# trabalho.net
KiCad netlist of a schematic drawn in EAGLE
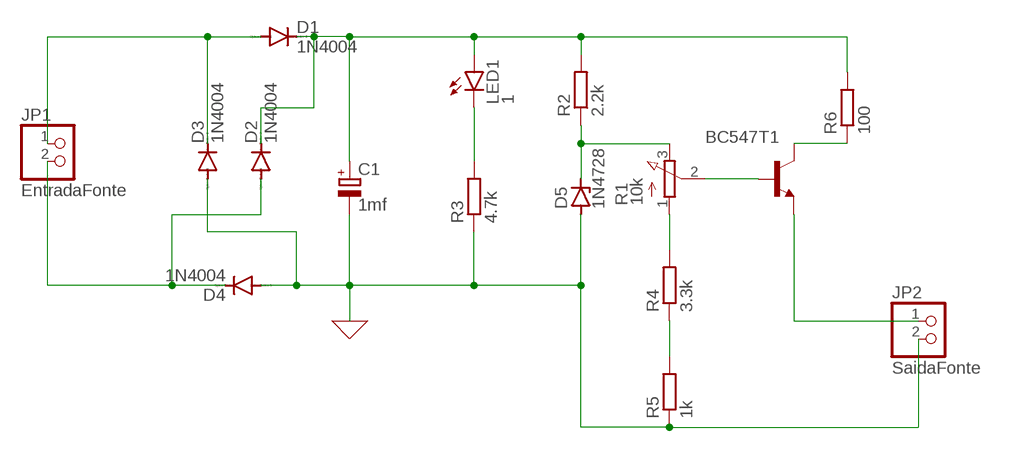
[diagram p0: schematic, sheet 1]

(export (version "E")
  (design (tool "Eeschema 10.0.6"))
  (components
    (comp (ref "C1")
      (value "1mf")
      (footprint "eagle-import:E5-10,5")
      (libsource (lib "eagle-import") (part "CPOL-EUE5-10.5"))
    )
    (comp (ref "D1")
      (value "1N4004")
      (footprint "eagle-import:DO41-10")
      (libsource (lib "eagle-import") (part "1N4004"))
    )
    (comp (ref "D2")
      (value "1N4004")
      (footprint "eagle-import:DO41-10")
      (libsource (lib "eagle-import") (part "1N4004"))
    )
    (comp (ref "D3")
      (value "1N4004")
      (footprint "eagle-import:DO41-10")
      (libsource (lib "eagle-import") (part "1N4004"))
    )
    (comp (ref "D4")
      (value "1N4004")
      (footprint "eagle-import:DO41-10")
      (libsource (lib "eagle-import") (part "1N4004"))
    )
    (comp (ref "D5")
      (value "1N4728")
      (footprint "eagle-import:DO41Z10")
      (libsource (lib "eagle-import") (part "1N4728"))
    )
    (comp (ref "JP1")
      (value "EntradaFonte")
      (footprint "eagle-import:1X02")
      (libsource (lib "eagle-import") (part "PINHD-1X2"))
    )
    (comp (ref "JP2")
      (value "SaidaFonte")
      (footprint "eagle-import:1X02")
      (libsource (lib "eagle-import") (part "PINHD-1X2"))
    )
    (comp (ref "LED1")
      (value "1")
      (footprint "eagle-import:LED5MM")
      (libsource (lib "eagle-import") (part "LED5MM"))
    )
    (comp (ref "R1")
      (value "10k")
      (footprint "eagle-import:3RP_1610N")
      (libsource (lib "eagle-import") (part "3RP/1610N"))
    )
    (comp (ref "R2")
      (value "2.2k")
      (footprint "eagle-import:0207_10")
      (libsource (lib "eagle-import") (part "R-EU_0207/10"))
    )
    (comp (ref "R3")
      (value "4.7k")
      (footprint "eagle-import:0207_10")
      (libsource (lib "eagle-import") (part "R-EU_0207/10"))
    )
    (comp (ref "R4")
      (value "3.3k")
      (footprint "eagle-import:0207_10")
      (libsource (lib "eagle-import") (part "R-EU_0207/10"))
    )
    (comp (ref "R5")
      (value "1k")
      (footprint "eagle-import:0207_10")
      (libsource (lib "eagle-import") (part "R-EU_0207/10"))
    )
    (comp (ref "R6")
      (value "100")
      (footprint "eagle-import:0207_10")
      (libsource (lib "eagle-import") (part "R-EU_0207/10"))
    )
    (comp (ref "T1")
      (value "BC547")
      (footprint "eagle-import:TO92")
      (libsource (lib "eagle-import") (part "BC547"))
    )
  )
  (nets
    (net (code "1") (name "GND") (class "Default")
      (node (ref "C1") (pin "-") (pinfunction "-_-") (pintype "passive"))
      (node (ref "D3") (pin "A") (pinfunction "A_A") (pintype "passive"))
      (node (ref "D4") (pin "A") (pinfunction "A_A") (pintype "passive"))
      (node (ref "D5") (pin "A") (pinfunction "A_A") (pintype "passive"))
      (node (ref "JP2") (pin "2") (pinfunction "2_2") (pintype "passive"))
      (node (ref "R3") (pin "1") (pinfunction "1_1") (pintype "passive"))
      (node (ref "R5") (pin "1") (pinfunction "1_1") (pintype "passive"))
    )
    (net (code "2") (name "Net-(C1-Pad+)") (class "Default")
      (node (ref "C1") (pin "+") (pinfunction "+_+") (pintype "passive"))
      (node (ref "D1") (pin "C") (pinfunction "C_C") (pintype "passive"))
      (node (ref "D2") (pin "C") (pinfunction "C_C") (pintype "passive"))
      (node (ref "LED1") (pin "A") (pinfunction "A_A") (pintype "passive"))
      (node (ref "R2") (pin "2") (pinfunction "2_2") (pintype "passive"))
      (node (ref "R6") (pin "2") (pinfunction "2_2") (pintype "passive"))
    )
    (net (code "3") (name "Net-(D1-PadA)") (class "Default")
      (node (ref "D1") (pin "A") (pinfunction "A_A") (pintype "passive"))
      (node (ref "D3") (pin "C") (pinfunction "C_C") (pintype "passive"))
      (node (ref "JP1") (pin "1") (pinfunction "1_1") (pintype "passive"))
    )
    (net (code "4") (name "Net-(D2-PadA)") (class "Default")
      (node (ref "D2") (pin "A") (pinfunction "A_A") (pintype "passive"))
      (node (ref "D4") (pin "C") (pinfunction "C_C") (pintype "passive"))
      (node (ref "JP1") (pin "2") (pinfunction "2_2") (pintype "passive"))
    )
    (net (code "5") (name "Net-(LED1-C)") (class "Default")
      (node (ref "LED1") (pin "K") (pinfunction "C_K") (pintype "passive"))
      (node (ref "R3") (pin "2") (pinfunction "2_2") (pintype "passive"))
    )
    (net (code "6") (name "Net-(R1-A)") (class "Default")
      (node (ref "R1") (pin "1") (pinfunction "A_1") (pintype "passive"))
      (node (ref "R4") (pin "2") (pinfunction "2_2") (pintype "passive"))
    )
    (net (code "7") (name "Net-(R1-E)") (class "Default")
      (node (ref "D5") (pin "C") (pinfunction "C_C") (pintype "passive"))
      (node (ref "R1") (pin "3") (pinfunction "E_3") (pintype "passive"))
      (node (ref "R2") (pin "1") (pinfunction "1_1") (pintype "passive"))
    )
    (net (code "8") (name "Net-(R1-S)") (class "Default")
      (node (ref "R1") (pin "2") (pinfunction "S_2") (pintype "passive"))
      (node (ref "T1") (pin "2") (pinfunction "B_2") (pintype "passive"))
    )
    (net (code "9") (name "Net-(R4-Pad1)") (class "Default")
      (node (ref "R4") (pin "1") (pinfunction "1_1") (pintype "passive"))
      (node (ref "R5") (pin "2") (pinfunction "2_2") (pintype "passive"))
    )
    (net (code "10") (name "Net-(T1-C)") (class "Default")
      (node (ref "R6") (pin "1") (pinfunction "1_1") (pintype "passive"))
      (node (ref "T1") (pin "3") (pinfunction "C_3") (pintype "passive"))
    )
    (net (code "11") (name "Net-(T1-E)") (class "Default")
      (node (ref "JP2") (pin "1") (pinfunction "1_1") (pintype "passive"))
      (node (ref "T1") (pin "1") (pinfunction "E_1") (pintype "passive"))
    )
  )
)
